# 1_DC_DC.net
KiCad netlist of a schematic drawn in Altium Designer
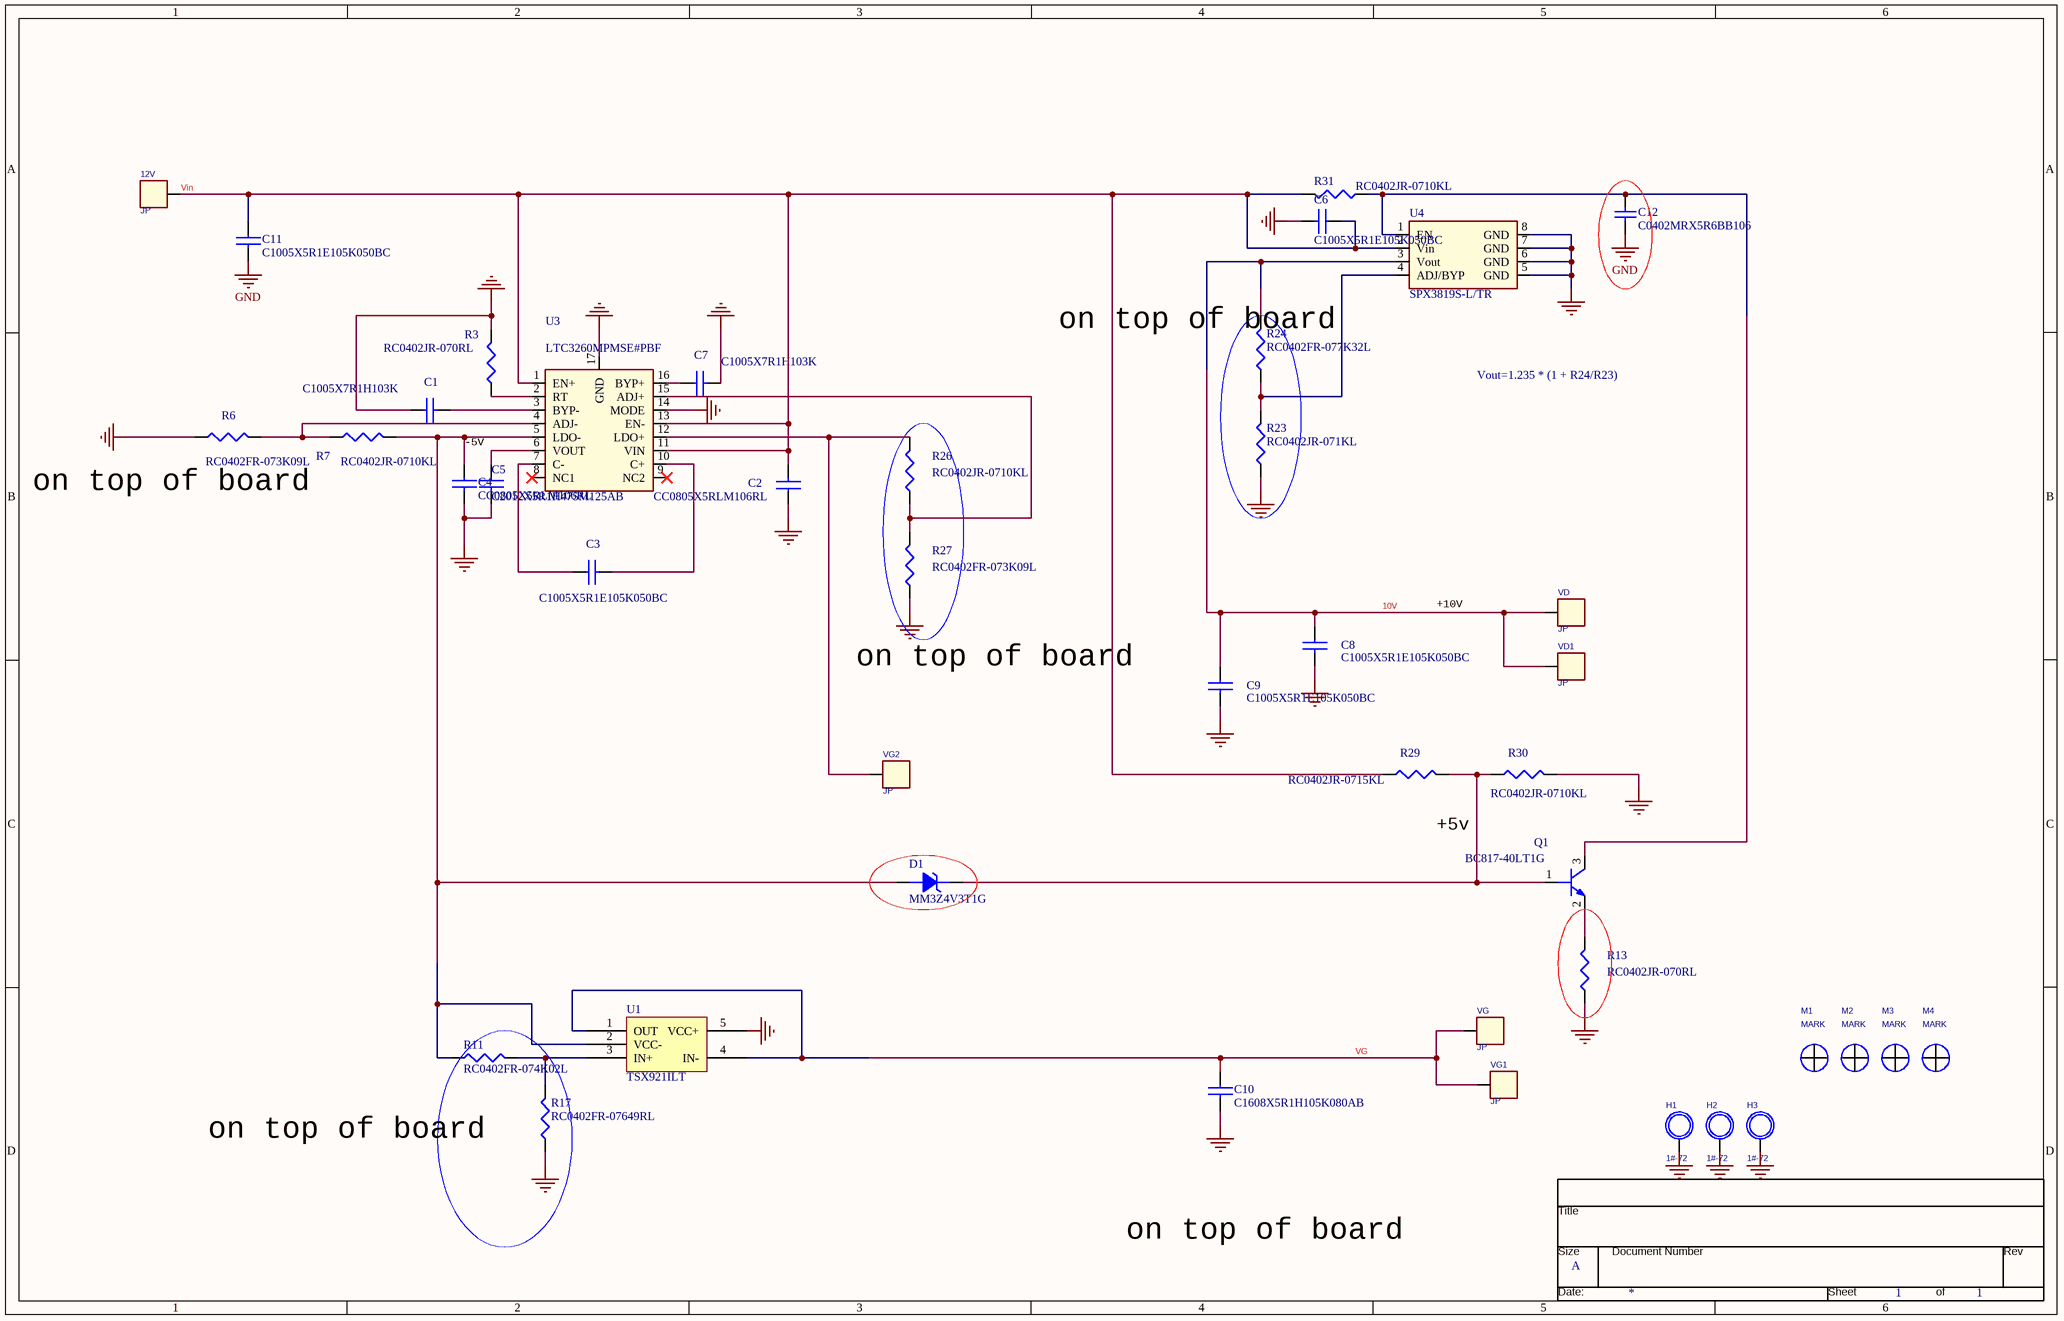
[diagram p0: 1) DC_DC.SchDoc]

(export (version "E")
  (design (tool "Eeschema 10.0.6"))
  (components
    (comp (ref "*")
      (value "TitleBlock0")
      (fields (field (name "PAGE COUNT") "1") (field (name "PAGE NUMBER") "1") (field (name "PAGE SIZE") "A"))
      (libsource (lib "*") (part "TitleBlock0"))
    )
    (comp (ref "12V") (value "JP") (footprint "JP_2.5X1.8") (libsource (lib "") (part "JP_1")))
    (comp (ref "C1")
      (value "C1005X7R1H103K")
      (footprint "C0402")
      (description "贴片电容_X7R_50V_0.01UF_±10%")
      (libsource (lib "TDK") (part "C1005X7R1H103K050BB"))
    )
    (comp (ref "C2")
      (value "CC0805X5RLM106RL")
      (footprint "C0805")
      (description "Ceramic_10uF_20%_X5R_35V")
      (libsource (lib "CCT") (part "CC0805X5RLM106RL"))
    )
    (comp (ref "C3")
      (value "C1005X5R1E105K050BC")
      (footprint "C0402")
      (description "0402_1UF_25V_±10%")
      (libsource (lib "TDK") (part "C1005X5R1E105K050BC"))
    )
    (comp (ref "C4")
      (value "CC0805X5RLM106RL")
      (footprint "C0805")
      (description "Ceramic_10uF_20%_X5R_35V")
      (libsource (lib "CCT") (part "CC0805X5RLM106RL"))
    )
    (comp (ref "C5")
      (value "C2012X5R1H475M125AB")
      (footprint "C0805")
      (description "0805_4.7UF 50V ±20％")
      (libsource (lib "TDK") (part "C2012X5R1H475M125AB"))
    )
    (comp (ref "C6")
      (value "C1005X5R1E105K050BC")
      (footprint "C0402")
      (description "0402_1UF_25V_±10%")
      (libsource (lib "TDK") (part "C1005X5R1E105K050BC"))
    )
    (comp (ref "C7")
      (value "C1005X7R1H103K")
      (footprint "C0402")
      (description "贴片电容_X7R_50V_0.01UF_±10%")
      (libsource (lib "TDK") (part "C1005X7R1H103K050BB"))
    )
    (comp (ref "C8")
      (value "C1005X5R1E105K050BC")
      (footprint "C0402")
      (description "0402_1UF_25V_±10%")
      (libsource (lib "TDK") (part "C1005X5R1E105K050BC"))
    )
    (comp (ref "C9")
      (value "C1005X5R1E105K050BC")
      (footprint "C0402")
      (description "0402_1UF_25V_±10%")
      (libsource (lib "TDK") (part "C1005X5R1E105K050BC"))
    )
    (comp (ref "C10")
      (value "C1608X5R1H105K080AB")
      (footprint "C0603")
      (description "0603_1UF_50V")
      (libsource (lib "TDK") (part "C1608X5R1H105K080AB"))
    )
    (comp (ref "C11")
      (value "C1005X5R1E105K050BC")
      (footprint "C0402")
      (description "0402_1UF_25V_±10%")
      (libsource (lib "TDK") (part "C1005X5R1E105K050BC"))
    )
    (comp (ref "C12")
      (value "C0402MRX5R6BB106")
      (footprint "C0402")
      (description "Ceramic_10000000pF_20%_10V_ppm/℃")
      (fields (field (name "PARTNO") "1245000136"))
      (libsource (lib "QOTANA_AD") (part "General-capacitor1"))
    )
    (comp (ref "D1")
      (value "MM3Z4V3T1G")
      (footprint "SOD-323")
      (description "通用二极管_稳压二极管_4.3V_200mW")
      (libsource (lib "ONSEMI") (part "MM3Z4V3T1G"))
    )
    (comp (ref "H1") (value "1#-72") (footprint "P3.2-1.8") (libsource (lib "JX") (part "1#-72")))
    (comp (ref "H2") (value "1#-72") (footprint "P3.2-1.8") (libsource (lib "JX") (part "1#-72")))
    (comp (ref "H3") (value "1#-72") (footprint "P3.2-1.8") (libsource (lib "JX") (part "1#-72")))
    (comp (ref "M1") (value "MARK") (libsource (lib "JX") (part "MARK")))
    (comp (ref "M2") (value "MARK") (libsource (lib "JX") (part "MARK")))
    (comp (ref "M3") (value "MARK") (libsource (lib "JX") (part "MARK")))
    (comp (ref "M4") (value "MARK") (libsource (lib "JX") (part "MARK")))
    (comp (ref "Q1")
      (value "BC817-40LT1G")
      (footprint "SOT-23")
      (description "通用BJT_NPN_45V_0.5A")
      (libsource (lib "ONSEMI") (part "BC817-40LT1G"))
    )
    (comp (ref "R3")
      (value "RC0402JR-070RL")
      (footprint "R0402")
      (description "0402_0Ω_1/16W_±1%")
      (libsource (lib "YAGEO") (part "RC0402JR-070RL"))
    )
    (comp (ref "R6")
      (value "RC0402FR-073K09L")
      (footprint "R0402")
      (description "0402-3.09K ±1%")
      (libsource (lib "YAGEO") (part "RC0402FR-073K09L"))
    )
    (comp (ref "R7")
      (value "RC0402JR-0710KL")
      (footprint "R0402")
      (description "Thick Film-SMD/SMT_10kΩ_5%")
      (libsource (lib "YAGEO") (part "RC0402JR-0710KL"))
    )
    (comp (ref "R11")
      (value "RC0402FR-074K02L")
      (footprint "R0402")
      (description "0402_4.02K_±1%")
      (libsource (lib "YAGEO") (part "RC0402FR-074K02L"))
    )
    (comp (ref "R13")
      (value "RC0402JR-070RL")
      (footprint "R0402")
      (description "General Purpose Resistors_0Ω_0±%_0.0625W")
      (fields (field (name "PARTNO") "1231000567"))
      (libsource (lib "QOTANA_AD") (part "General-resistors"))
    )
    (comp (ref "R17")
      (value "RC0402FR-07649RL")
      (footprint "R0402")
      (description "0402-649Ω-±1%")
      (libsource (lib "YAGEO") (part "RC0402FR-07649RL"))
    )
    (comp (ref "R23")
      (value "RC0402JR-071KL")
      (footprint "R0402")
      (description "贴片电阻_1KΩ_5%_100ppm_50V_1/16W")
      (libsource (lib "YAGEO") (part "RC0402JR-071KL"))
    )
    (comp (ref "R24")
      (value "RC0402FR-077K32L")
      (footprint "R0402")
      (description "0402_7.32K_1/16W_±1%")
      (libsource (lib "YAGEO") (part "RC0402FR-077K32L"))
    )
    (comp (ref "R26")
      (value "RC0402JR-0710KL")
      (footprint "R0402")
      (description "Thick Film-SMD/SMT_10kΩ_5%")
      (libsource (lib "YAGEO") (part "RC0402JR-0710KL"))
    )
    (comp (ref "R27")
      (value "RC0402FR-073K09L")
      (footprint "R0402")
      (description "0402-3.09K ±1%")
      (libsource (lib "YAGEO") (part "RC0402FR-073K09L"))
    )
    (comp (ref "R29")
      (value "RC0402JR-0715KL")
      (footprint "R0402")
      (description "0402_15K_±5%")
      (libsource (lib "YAGEO") (part "RC0402JR-0715KL"))
    )
    (comp (ref "R30")
      (value "RC0402JR-0710KL")
      (footprint "R0402")
      (description "Thick Film-SMD/SMT_10kΩ_5%")
      (libsource (lib "YAGEO") (part "RC0402JR-0710KL"))
    )
    (comp (ref "R31")
      (value "RC0402JR-0710KL")
      (footprint "R0402")
      (description "Thick Film-SMD/SMT_10kΩ_5%")
      (libsource (lib "YAGEO") (part "RC0402JR-0710KL"))
    )
    (comp (ref "U1") (value "TSX921ILT") (footprint "SOT-23-5") (libsource (lib "ST") (part "TSX921ILT")))
    (comp (ref "U3")
      (value "LTC3260MPMSE#PBF")
      (footprint "MSOP-16-EP")
      (description "电源IC_双极性输出电荷泵_4.5～32V_100mA")
      (libsource (lib "LT") (part "LTC3260EMSE"))
    )
    (comp (ref "U4")
      (value "SPX3819S-L/TR")
      (footprint "SOIC-8")
      (description "IC REG LIN POS ADJ 500MA 8SOIC")
      (libsource (lib "MAXIM") (part "SPX3819S-L/TR"))
    )
    (comp (ref "VD") (value "JP") (footprint "P3.2") (libsource (lib "JX") (part "JP")))
    (comp (ref "VD1") (value "JP") (footprint "P3.2") (libsource (lib "JX") (part "JP")))
    (comp (ref "VG") (value "JP") (footprint "P3.2") (libsource (lib "JX") (part "JP")))
    (comp (ref "VG1") (value "JP") (footprint "P3.2") (libsource (lib "JX") (part "JP")))
    (comp (ref "VG2") (value "JP") (footprint "JP_1.5X1.5") (libsource (lib "JX") (part "JP")))
  )
  (nets
    (net (code "1") (name "/10V") (class "Default")
      (node (ref "C8") (pin "1") (pinfunction "1_1") (pintype "passive"))
      (node (ref "C9") (pin "1") (pinfunction "1_1") (pintype "passive"))
      (node (ref "R24") (pin "2") (pinfunction "2_2") (pintype "passive"))
      (node (ref "U4") (pin "3") (pinfunction "Vout_3") (pintype "passive"))
      (node (ref "VD") (pin "1") (pinfunction "1_1") (pintype "passive"))
      (node (ref "VD1") (pin "1") (pinfunction "1_1") (pintype "passive"))
    )
    (net (code "2") (name "/VG") (class "Default")
      (node (ref "C10") (pin "1") (pinfunction "1_1") (pintype "passive"))
      (node (ref "U1") (pin "1") (pinfunction "OUT_1") (pintype "passive"))
      (node (ref "U1") (pin "4") (pinfunction "IN-_4") (pintype "passive"))
      (node (ref "VG") (pin "1") (pinfunction "1_1") (pintype "passive"))
      (node (ref "VG1") (pin "1") (pinfunction "1_1") (pintype "passive"))
    )
    (net (code "3") (name "/Vin") (class "Default")
      (node (ref "12V") (pin "1") (pinfunction "1_1") (pintype "passive"))
      (node (ref "C11") (pin "1") (pinfunction "1_1") (pintype "passive"))
      (node (ref "C2") (pin "2") (pinfunction "2_2") (pintype "passive"))
      (node (ref "C6") (pin "1") (pinfunction "1_1") (pintype "passive"))
      (node (ref "R29") (pin "2") (pinfunction "2_2") (pintype "passive"))
      (node (ref "R31") (pin "2") (pinfunction "2_2") (pintype "passive"))
      (node (ref "U3") (pin "1") (pinfunction "EN+_1") (pintype "passive"))
      (node (ref "U3") (pin "11") (pinfunction "VIN_11") (pintype "passive"))
      (node (ref "U3") (pin "13") (pinfunction "EN-_13") (pintype "passive"))
      (node (ref "U4") (pin "2") (pinfunction "Vin_2") (pintype "passive"))
    )
    (net (code "4") (name "GND") (class "Default")
      (node (ref "C1") (pin "1") (pinfunction "1_1") (pintype "passive"))
      (node (ref "C10") (pin "2") (pinfunction "2_2") (pintype "passive"))
      (node (ref "C11") (pin "2") (pinfunction "2_2") (pintype "passive"))
      (node (ref "C12") (pin "2") (pinfunction "2_2") (pintype "passive"))
      (node (ref "C2") (pin "1") (pinfunction "1_1") (pintype "passive"))
      (node (ref "C4") (pin "2") (pinfunction "2_2") (pintype "passive"))
      (node (ref "C5") (pin "2") (pinfunction "2_2") (pintype "passive"))
      (node (ref "C6") (pin "2") (pinfunction "2_2") (pintype "passive"))
      (node (ref "C7") (pin "2") (pinfunction "2_2") (pintype "passive"))
      (node (ref "C8") (pin "2") (pinfunction "2_2") (pintype "passive"))
      (node (ref "C9") (pin "2") (pinfunction "2_2") (pintype "passive"))
      (node (ref "H1") (pin "1") (pinfunction "1_1") (pintype "passive"))
      (node (ref "H2") (pin "1") (pinfunction "1_1") (pintype "passive"))
      (node (ref "H3") (pin "1") (pinfunction "1_1") (pintype "passive"))
      (node (ref "R13") (pin "1") (pinfunction "1_1") (pintype "passive"))
      (node (ref "R17") (pin "1") (pinfunction "1_1") (pintype "passive"))
      (node (ref "R23") (pin "1") (pinfunction "1_1") (pintype "passive"))
      (node (ref "R27") (pin "1") (pinfunction "1_1") (pintype "passive"))
      (node (ref "R3") (pin "2") (pinfunction "2_2") (pintype "passive"))
      (node (ref "R30") (pin "1") (pinfunction "1_1") (pintype "passive"))
      (node (ref "R6") (pin "1") (pinfunction "1_1") (pintype "passive"))
      (node (ref "U1") (pin "5") (pinfunction "VCC+_5") (pintype "passive"))
      (node (ref "U3") (pin "14") (pinfunction "MODE_14") (pintype "passive"))
      (node (ref "U3") (pin "17") (pinfunction "GND_17") (pintype "passive"))
      (node (ref "U4") (pin "5") (pinfunction "GND_5") (pintype "passive"))
      (node (ref "U4") (pin "6") (pinfunction "GND_6") (pintype "passive"))
      (node (ref "U4") (pin "7") (pinfunction "GND_7") (pintype "passive"))
      (node (ref "U4") (pin "8") (pinfunction "GND_8") (pintype "passive"))
    )
    (net (code "5") (name "Net-(Q1-B)") (class "Default")
      (node (ref "D1") (pin "1") (pinfunction "1_1") (pintype "passive"))
      (node (ref "Q1") (pin "1") (pinfunction "B_1") (pintype "passive"))
      (node (ref "R29") (pin "1") (pinfunction "1_1") (pintype "passive"))
      (node (ref "R30") (pin "2") (pinfunction "2_2") (pintype "passive"))
    )
    (net (code "6") (name "Net-(Q1-C)") (class "Default")
      (node (ref "C12") (pin "1") (pinfunction "1_1") (pintype "passive"))
      (node (ref "Q1") (pin "3") (pinfunction "C_3") (pintype "passive"))
      (node (ref "R31") (pin "1") (pinfunction "1_1") (pintype "passive"))
      (node (ref "U4") (pin "1") (pinfunction "EN_1") (pintype "passive"))
    )
    (net (code "7") (name "Net-(Q1-E)") (class "Default")
      (node (ref "Q1") (pin "2") (pinfunction "E_2") (pintype "passive"))
      (node (ref "R13") (pin "2") (pinfunction "2_2") (pintype "passive"))
    )
    (net (code "8") (name "Net-(U1-IN+)") (class "Default")
      (node (ref "R11") (pin "2") (pinfunction "2_2") (pintype "passive"))
      (node (ref "R17") (pin "2") (pinfunction "2_2") (pintype "passive"))
      (node (ref "U1") (pin "3") (pinfunction "IN+_3") (pintype "passive"))
    )
    (net (code "9") (name "Net-(U1-VCC-)") (class "Default")
      (node (ref "C4") (pin "1") (pinfunction "1_1") (pintype "passive"))
      (node (ref "D1") (pin "2") (pinfunction "2_2") (pintype "passive"))
      (node (ref "R11") (pin "1") (pinfunction "1_1") (pintype "passive"))
      (node (ref "R7") (pin "2") (pinfunction "2_2") (pintype "passive"))
      (node (ref "U1") (pin "2") (pinfunction "VCC-_2") (pintype "passive"))
      (node (ref "U3") (pin "5") (pinfunction "LDO-_5") (pintype "passive"))
    )
    (net (code "10") (name "Net-(U3-ADJ+)") (class "Default")
      (node (ref "R26") (pin "1") (pinfunction "1_1") (pintype "passive"))
      (node (ref "R27") (pin "2") (pinfunction "2_2") (pintype "passive"))
      (node (ref "U3") (pin "15") (pinfunction "ADJ+_15") (pintype "passive"))
    )
    (net (code "11") (name "Net-(U3-ADJ-)") (class "Default")
      (node (ref "R6") (pin "2") (pinfunction "2_2") (pintype "passive"))
      (node (ref "R7") (pin "1") (pinfunction "1_1") (pintype "passive"))
      (node (ref "U3") (pin "4") (pinfunction "ADJ-_4") (pintype "passive"))
    )
    (net (code "12") (name "Net-(U3-BYP+)") (class "Default")
      (node (ref "C7") (pin "1") (pinfunction "1_1") (pintype "passive"))
      (node (ref "U3") (pin "16") (pinfunction "BYP+_16") (pintype "passive"))
    )
    (net (code "13") (name "Net-(U3-BYP-)") (class "Default")
      (node (ref "C1") (pin "2") (pinfunction "2_2") (pintype "passive"))
      (node (ref "U3") (pin "3") (pinfunction "BYP-_3") (pintype "passive"))
    )
    (net (code "14") (name "Net-(U3-C+)") (class "Default")
      (node (ref "C3") (pin "2") (pinfunction "2_2") (pintype "passive"))
      (node (ref "U3") (pin "10") (pinfunction "C+_10") (pintype "passive"))
    )
    (net (code "15") (name "Net-(U3-C-)") (class "Default")
      (node (ref "C3") (pin "1") (pinfunction "1_1") (pintype "passive"))
      (node (ref "U3") (pin "7") (pinfunction "C-_7") (pintype "passive"))
    )
    (net (code "16") (name "Net-(U3-LDO+)") (class "Default")
      (node (ref "R26") (pin "2") (pinfunction "2_2") (pintype "passive"))
      (node (ref "U3") (pin "12") (pinfunction "LDO+_12") (pintype "passive"))
      (node (ref "VG2") (pin "1") (pinfunction "1_1") (pintype "passive"))
    )
    (net (code "17") (name "Net-(U3-RT)") (class "Default")
      (node (ref "R3") (pin "1") (pinfunction "1_1") (pintype "passive"))
      (node (ref "U3") (pin "2") (pinfunction "RT_2") (pintype "passive"))
    )
    (net (code "18") (name "Net-(U3-VOUT)") (class "Default")
      (node (ref "C5") (pin "1") (pinfunction "1_1") (pintype "passive"))
      (node (ref "U3") (pin "6") (pinfunction "VOUT_6") (pintype "passive"))
    )
    (net (code "19") (name "Net-(U4-ADJ{slash}BYP)") (class "Default")
      (node (ref "R23") (pin "2") (pinfunction "2_2") (pintype "passive"))
      (node (ref "R24") (pin "1") (pinfunction "1_1") (pintype "passive"))
      (node (ref "U4") (pin "4") (pinfunction "ADJ/BYP_4") (pintype "passive"))
    )
    (net (code "20") (name "unconnected-(M1-Pad1)") (class "Default")
      (node (ref "M1") (pin "1") (pinfunction "1_1") (pintype "passive"))
    )
    (net (code "21") (name "unconnected-(M2-Pad1)") (class "Default")
      (node (ref "M2") (pin "1") (pinfunction "1_1") (pintype "passive"))
    )
    (net (code "22") (name "unconnected-(M3-Pad1)") (class "Default")
      (node (ref "M3") (pin "1") (pinfunction "1_1") (pintype "passive"))
    )
    (net (code "23") (name "unconnected-(M4-Pad1)") (class "Default")
      (node (ref "M4") (pin "1") (pinfunction "1_1") (pintype "passive"))
    )
    (net (code "24") (name "unconnected-(U3-NC1-Pad8)") (class "Default")
      (node (ref "U3") (pin "8") (pinfunction "NC1_8") (pintype "passive+no_connect"))
    )
    (net (code "25") (name "unconnected-(U3-NC2-Pad9)") (class "Default")
      (node (ref "U3") (pin "9") (pinfunction "NC2_9") (pintype "passive+no_connect"))
    )
  )
)
